# micon_sensor.net
KiCad netlist of a schematic drawn in EAGLE
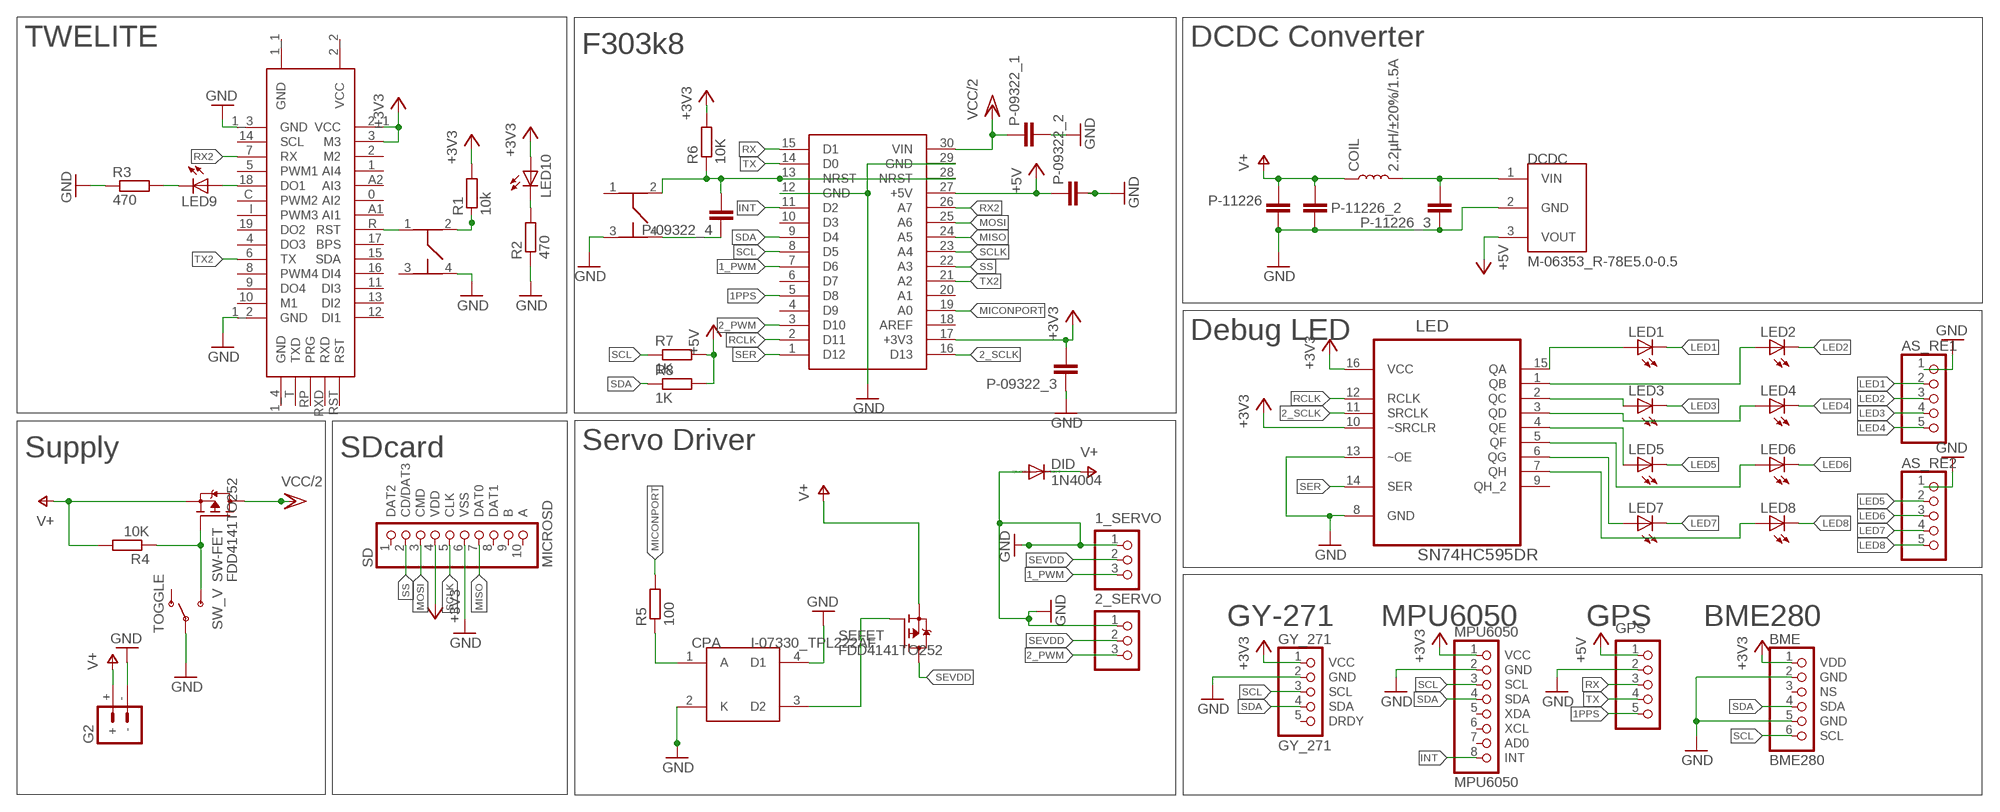
[diagram p0: schematic, sheet 1]

(export (version "E")
  (design (tool "Eeschema 10.0.6"))
  (components
    (comp (ref "1_SERVO")
      (value "B3B-XH-A")
      (footprint "eagle-import:B3B-XH-A")
      (libsource (lib "eagle-import") (part "B3B-XH-A"))
    )
    (comp (ref "2_SERVO")
      (value "B3B-XH-A")
      (footprint "eagle-import:B3B-XH-A")
      (libsource (lib "eagle-import") (part "B3B-XH-A"))
    )
    (comp (ref "AS_RE1")
      (value "PINHD-1X5")
      (footprint "eagle-import:1X05")
      (libsource (lib "eagle-import") (part "PINHD-1X5"))
    )
    (comp (ref "AS_RE2")
      (value "PINHD-1X5")
      (footprint "eagle-import:1X05")
      (libsource (lib "eagle-import") (part "PINHD-1X5"))
    )
    (comp (ref "BME")
      (value "BME280")
      (footprint "eagle-import:1X06")
      (libsource (lib "eagle-import") (part "BME280"))
    )
    (comp (ref "COIL")
      (value "2.2µH/±20%/1.5A")
      (footprint "eagle-import:INDUCTOR_2.2UH")
      (libsource (lib "eagle-import") (part "INDUCTOR-VLF4012AT-2.2UH"))
    )
    (comp (ref "CPA")
      (value "I-07330_TPL222AF")
      (footprint "eagle-import:TLP222AF")
      (libsource (lib "eagle-import") (part "I-07330_TPL222AF"))
    )
    (comp (ref "DCDC")
      (value "M-06353_R-78E5.0-0.5")
      (footprint "eagle-import:R-78E5.0-0.5")
      (libsource (lib "eagle-import") (part "M-06353_R-78E5.0-0.5"))
    )
    (comp (ref "DID")
      (value "1N4004")
      (footprint "eagle-import:DO41-10")
      (libsource (lib "eagle-import") (part "1N4004"))
    )
    (comp (ref "G2")
      (value "BATTERY_CONN_DEANS")
      (footprint "eagle-import:DEANS")
      (libsource (lib "eagle-import") (part "BATTERY_CONN_DEANS"))
    )
    (comp (ref "GPS")
      (value "B5B-XH-A")
      (footprint "eagle-import:B5B-XH-A")
      (libsource (lib "eagle-import") (part "B5B-XH-A"))
    )
    (comp (ref "GY_271")
      (value "GY_271")
      (footprint "eagle-import:1X05")
      (libsource (lib "eagle-import") (part "GY_271"))
    )
    (comp (ref "LED")
      (value "SN74HC595DR")
      (footprint "eagle-import:SOIC127P600X175-16N")
      (fields (field (name "MF") "Texas Instruments"))
      (libsource (lib "eagle-import") (part "SN74HC595DR"))
    )
    (comp (ref "LED1")
      (value "LEDCHIP-LED0603")
      (footprint "eagle-import:CHIP-LED0603")
      (libsource (lib "eagle-import") (part "LEDCHIP-LED0603"))
    )
    (comp (ref "LED2")
      (value "LEDCHIP-LED0603")
      (footprint "eagle-import:CHIP-LED0603")
      (libsource (lib "eagle-import") (part "LEDCHIP-LED0603"))
    )
    (comp (ref "LED3")
      (value "LEDCHIP-LED0603")
      (footprint "eagle-import:CHIP-LED0603")
      (libsource (lib "eagle-import") (part "LEDCHIP-LED0603"))
    )
    (comp (ref "LED4")
      (value "LEDCHIP-LED0603")
      (footprint "eagle-import:CHIP-LED0603")
      (libsource (lib "eagle-import") (part "LEDCHIP-LED0603"))
    )
    (comp (ref "LED5")
      (value "LEDCHIP-LED0603")
      (footprint "eagle-import:CHIP-LED0603")
      (libsource (lib "eagle-import") (part "LEDCHIP-LED0603"))
    )
    (comp (ref "LED6")
      (value "LEDCHIP-LED0603")
      (footprint "eagle-import:CHIP-LED0603")
      (libsource (lib "eagle-import") (part "LEDCHIP-LED0603"))
    )
    (comp (ref "LED7")
      (value "LEDCHIP-LED0603")
      (footprint "eagle-import:CHIP-LED0603")
      (libsource (lib "eagle-import") (part "LEDCHIP-LED0603"))
    )
    (comp (ref "LED8")
      (value "LEDCHIP-LED0603")
      (footprint "eagle-import:CHIP-LED0603")
      (libsource (lib "eagle-import") (part "LEDCHIP-LED0603"))
    )
    (comp (ref "LED9")
      (value "LEDCHIP-LED0603")
      (footprint "eagle-import:CHIP-LED0603")
      (libsource (lib "eagle-import") (part "LEDCHIP-LED0603"))
    )
    (comp (ref "LED10")
      (value "LEDCHIP-LED0603")
      (footprint "eagle-import:CHIP-LED0603")
      (libsource (lib "eagle-import") (part "LEDCHIP-LED0603"))
    )
    (comp (ref "MPU6050")
      (value "MPU6050")
      (footprint "eagle-import:1X08")
      (libsource (lib "eagle-import") (part "MPU6050"))
    )
    (comp (ref "P-09322_1")
      (value "C-EUC0805")
      (footprint "eagle-import:C0805")
      (libsource (lib "eagle-import") (part "C-EUC0805"))
    )
    (comp (ref "P-09322_2")
      (value "C-EUC0805")
      (footprint "eagle-import:C0805")
      (libsource (lib "eagle-import") (part "C-EUC0805"))
    )
    (comp (ref "P-09322_3")
      (value "C-EUC0805")
      (footprint "eagle-import:C0805")
      (libsource (lib "eagle-import") (part "C-EUC0805"))
    )
    (comp (ref "P-09322_4")
      (value "C-EUC0805")
      (footprint "eagle-import:C0805")
      (libsource (lib "eagle-import") (part "C-EUC0805"))
    )
    (comp (ref "P-11226")
      (value "C-EUC0805")
      (footprint "eagle-import:C0805")
      (libsource (lib "eagle-import") (part "C-EUC0805"))
    )
    (comp (ref "P-11226_2")
      (value "C-EUC0805")
      (footprint "eagle-import:C0805")
      (libsource (lib "eagle-import") (part "C-EUC0805"))
    )
    (comp (ref "P-11226_3")
      (value "C-EUC0805")
      (footprint "eagle-import:C0805")
      (libsource (lib "eagle-import") (part "C-EUC0805"))
    )
    (comp (ref "R1")
      (value "10k")
      (footprint "eagle-import:R0805")
      (libsource (lib "eagle-import") (part "R-EU_R0805"))
    )
    (comp (ref "R2")
      (value "470")
      (footprint "eagle-import:R0805")
      (libsource (lib "eagle-import") (part "R-EU_R0805"))
    )
    (comp (ref "R3")
      (value "470")
      (footprint "eagle-import:R0805")
      (libsource (lib "eagle-import") (part "R-EU_R0805"))
    )
    (comp (ref "R4")
      (value "10K")
      (footprint "eagle-import:R0805")
      (libsource (lib "eagle-import") (part "R-EU_R0805"))
    )
    (comp (ref "R5")
      (value "100")
      (footprint "eagle-import:R0805")
      (libsource (lib "eagle-import") (part "R-EU_R0805"))
    )
    (comp (ref "R6")
      (value "10K")
      (footprint "eagle-import:R0805")
      (libsource (lib "eagle-import") (part "R-EU_R0805"))
    )
    (comp (ref "R7")
      (value "1K")
      (footprint "eagle-import:R0805")
      (libsource (lib "eagle-import") (part "R-EU_R0805"))
    )
    (comp (ref "R8")
      (value "1K")
      (footprint "eagle-import:R0805")
      (libsource (lib "eagle-import") (part "R-EU_R0805"))
    )
    (comp (ref "SD")
      (value "MICROSD")
      (footprint "eagle-import:1X10")
      (libsource (lib "eagle-import") (part "MICROSD"))
    )
    (comp (ref "SEFET")
      (value "FDD4141TO252")
      (footprint "eagle-import:TO252")
      (libsource (lib "eagle-import") (part "FDD4141TO252"))
    )
    (comp (ref "SW-FET")
      (value "FDD4141TO252")
      (footprint "eagle-import:TO252")
      (libsource (lib "eagle-import") (part "FDD4141TO252"))
    )
    (comp (ref "SW_MI")
      (value "SWITCH")
      (footprint "eagle-import:SWITCH")
      (libsource (lib "eagle-import") (part "SWITCH"))
    )
    (comp (ref "SW_V")
      (value "TOGGLE")
      (footprint "eagle-import:320-916")
      (libsource (lib "eagle-import") (part "TOGGLE"))
    )
    (comp (ref "TWE_SW")
      (value "SWITCH")
      (footprint "eagle-import:SWITCH")
      (libsource (lib "eagle-import") (part "SWITCH"))
    )
    (comp (ref "U$1")
      (value "TWELITE")
      (footprint "eagle-import:TWELITE_DIP")
      (libsource (lib "eagle-import") (part "TWELITE"))
    )
    (comp (ref "U$3")
      (value "STM32F303K8")
      (footprint "eagle-import:STM32F303K8")
      (libsource (lib "eagle-import") (part "STM32F303K8"))
    )
  )
  (nets
    (net (code "1") (name "+3V3") (class "Default")
      (node (ref "BME") (pin "1") (pinfunction "VDD_1") (pintype "passive"))
      (node (ref "GY_271") (pin "1") (pinfunction "VCC_1") (pintype "passive"))
      (node (ref "LED") (pin "10") (pinfunction "~{SRCLR}_10") (pintype "input"))
      (node (ref "LED") (pin "16") (pinfunction "VCC_16") (pintype "power_in"))
      (node (ref "LED10") (pin "A") (pinfunction "A_A") (pintype "passive"))
      (node (ref "MPU6050") (pin "1") (pinfunction "VCC_1") (pintype "passive"))
      (node (ref "P-09322_3") (pin "2") (pinfunction "2_2") (pintype "passive"))
      (node (ref "R1") (pin "2") (pinfunction "2_2") (pintype "passive"))
      (node (ref "R6") (pin "2") (pinfunction "2_2") (pintype "passive"))
      (node (ref "SD") (pin "4") (pinfunction "VDD_4") (pintype "bidirectional"))
      (node (ref "U$1") (pin "2_1") (pinfunction "VCC_2_1") (pintype "bidirectional"))
      (node (ref "U$1") (pin "3") (pinfunction "M3_3") (pintype "bidirectional"))
      (node (ref "U$3") (pin "17") (pinfunction "+3V3_17") (pintype "power_in"))
    )
    (net (code "2") (name "+5V") (class "Default")
      (node (ref "DCDC") (pin "3") (pinfunction "VOUT_3") (pintype "bidirectional"))
      (node (ref "GPS") (pin "1") (pinfunction "1_1") (pintype "passive"))
      (node (ref "P-09322_2") (pin "1") (pinfunction "1_1") (pintype "passive"))
      (node (ref "R7") (pin "2") (pinfunction "2_2") (pintype "passive"))
      (node (ref "R8") (pin "2") (pinfunction "2_2") (pintype "passive"))
      (node (ref "U$3") (pin "27") (pinfunction "+5V_27") (pintype "power_in"))
    )
    (net (code "3") (name "/AREF") (class "Default")
      (node (ref "U$3") (pin "18") (pinfunction "AREF_18") (pintype "power_in"))
    )
    (net (code "4") (name "1PPS") (class "Default")
      (node (ref "GPS") (pin "5") (pinfunction "5_5") (pintype "passive"))
      (node (ref "U$3") (pin "5") (pinfunction "D8_5") (pintype "bidirectional"))
    )
    (net (code "5") (name "1_PWM") (class "Default")
      (node (ref "1_SERVO") (pin "3") (pinfunction "3_3") (pintype "passive"))
      (node (ref "U$3") (pin "7") (pinfunction "D6_7") (pintype "bidirectional"))
    )
    (net (code "6") (name "2_PWM") (class "Default")
      (node (ref "2_SERVO") (pin "3") (pinfunction "3_3") (pintype "passive"))
      (node (ref "U$3") (pin "3") (pinfunction "D10_3") (pintype "bidirectional"))
    )
    (net (code "7") (name "2_SCLK") (class "Default")
      (node (ref "LED") (pin "11") (pinfunction "SRCLK_11") (pintype "input"))
      (node (ref "U$3") (pin "16") (pinfunction "D13_16") (pintype "bidirectional"))
    )
    (net (code "8") (name "GND") (class "Default")
      (node (ref "1_SERVO") (pin "1") (pinfunction "1_1") (pintype "passive"))
      (node (ref "2_SERVO") (pin "1") (pinfunction "1_1") (pintype "passive"))
      (node (ref "AS_RE1") (pin "1") (pinfunction "1_1") (pintype "passive"))
      (node (ref "AS_RE2") (pin "1") (pinfunction "1_1") (pintype "passive"))
      (node (ref "BME") (pin "2") (pinfunction "GND_2") (pintype "passive"))
      (node (ref "BME") (pin "5") (pinfunction "GND_5") (pintype "passive"))
      (node (ref "CPA") (pin "2") (pinfunction "K_2") (pintype "bidirectional"))
      (node (ref "CPA") (pin "4") (pinfunction "D1_4") (pintype "bidirectional"))
      (node (ref "DCDC") (pin "2") (pinfunction "GND_2") (pintype "bidirectional"))
      (node (ref "DID") (pin "A") (pinfunction "A_A") (pintype "passive"))
      (node (ref "G2") (pin "-") (pinfunction "-_-") (pintype "passive"))
      (node (ref "GPS") (pin "2") (pinfunction "2_2") (pintype "passive"))
      (node (ref "GY_271") (pin "2") (pinfunction "GND_2") (pintype "passive"))
      (node (ref "LED") (pin "13") (pinfunction "~{OE}_13") (pintype "input"))
      (node (ref "LED") (pin "8") (pinfunction "GND_8") (pintype "passive"))
      (node (ref "MPU6050") (pin "2") (pinfunction "GND_2") (pintype "passive"))
      (node (ref "P-09322_1") (pin "2") (pinfunction "2_2") (pintype "passive"))
      (node (ref "P-09322_2") (pin "2") (pinfunction "2_2") (pintype "passive"))
      (node (ref "P-09322_3") (pin "1") (pinfunction "1_1") (pintype "passive"))
      (node (ref "P-11226") (pin "1") (pinfunction "1_1") (pintype "passive"))
      (node (ref "P-11226_2") (pin "1") (pinfunction "1_1") (pintype "passive"))
      (node (ref "P-11226_3") (pin "1") (pinfunction "1_1") (pintype "passive"))
      (node (ref "R2") (pin "1") (pinfunction "1_1") (pintype "passive"))
      (node (ref "R3") (pin "1") (pinfunction "1_1") (pintype "passive"))
      (node (ref "SD") (pin "6") (pinfunction "VSS_6") (pintype "bidirectional"))
      (node (ref "SW_MI") (pin "3") (pinfunction "P$3_3") (pintype "bidirectional"))
      (node (ref "SW_V") (pin "2") (pinfunction "2_2") (pintype "passive"))
      (node (ref "TWE_SW") (pin "4") (pinfunction "P$4_4") (pintype "bidirectional"))
      (node (ref "U$1") (pin "1_2") (pinfunction "GND_1_2") (pintype "bidirectional"))
      (node (ref "U$1") (pin "1_3") (pinfunction "GND_1_3") (pintype "bidirectional"))
      (node (ref "U$3") (pin "12") (pinfunction "GND_12") (pintype "power_in"))
      (node (ref "U$3") (pin "29") (pinfunction "GND_29") (pintype "power_in"))
    )
    (net (code "9") (name "INT") (class "Default")
      (node (ref "MPU6050") (pin "8") (pinfunction "INT_8") (pintype "passive"))
      (node (ref "U$3") (pin "11") (pinfunction "D2_11") (pintype "bidirectional"))
    )
    (net (code "10") (name "LED1") (class "Default")
      (node (ref "AS_RE1") (pin "2") (pinfunction "2_2") (pintype "passive"))
      (node (ref "LED1") (pin "C") (pinfunction "C_C") (pintype "passive"))
    )
    (net (code "11") (name "LED2") (class "Default")
      (node (ref "AS_RE1") (pin "3") (pinfunction "3_3") (pintype "passive"))
      (node (ref "LED2") (pin "C") (pinfunction "C_C") (pintype "passive"))
    )
    (net (code "12") (name "LED3") (class "Default")
      (node (ref "AS_RE1") (pin "4") (pinfunction "4_4") (pintype "passive"))
      (node (ref "LED3") (pin "C") (pinfunction "C_C") (pintype "passive"))
    )
    (net (code "13") (name "LED4") (class "Default")
      (node (ref "AS_RE1") (pin "5") (pinfunction "5_5") (pintype "passive"))
      (node (ref "LED4") (pin "C") (pinfunction "C_C") (pintype "passive"))
    )
    (net (code "14") (name "LED5") (class "Default")
      (node (ref "AS_RE2") (pin "2") (pinfunction "2_2") (pintype "passive"))
      (node (ref "LED5") (pin "C") (pinfunction "C_C") (pintype "passive"))
    )
    (net (code "15") (name "LED6") (class "Default")
      (node (ref "AS_RE2") (pin "3") (pinfunction "3_3") (pintype "passive"))
      (node (ref "LED6") (pin "C") (pinfunction "C_C") (pintype "passive"))
    )
    (net (code "16") (name "LED7") (class "Default")
      (node (ref "AS_RE2") (pin "4") (pinfunction "4_4") (pintype "passive"))
      (node (ref "LED7") (pin "C") (pinfunction "C_C") (pintype "passive"))
    )
    (net (code "17") (name "LED8") (class "Default")
      (node (ref "AS_RE2") (pin "5") (pinfunction "5_5") (pintype "passive"))
      (node (ref "LED8") (pin "C") (pinfunction "C_C") (pintype "passive"))
    )
    (net (code "18") (name "MICONPORT") (class "Default")
      (node (ref "R5") (pin "2") (pinfunction "2_2") (pintype "passive"))
      (node (ref "U$3") (pin "19") (pinfunction "A0_19") (pintype "bidirectional"))
    )
    (net (code "19") (name "MISO") (class "Default")
      (node (ref "SD") (pin "7") (pinfunction "DAT0_7") (pintype "bidirectional"))
      (node (ref "U$3") (pin "24") (pinfunction "A5_24") (pintype "bidirectional"))
    )
    (net (code "20") (name "MOSI") (class "Default")
      (node (ref "SD") (pin "3") (pinfunction "CMD_3") (pintype "bidirectional"))
      (node (ref "U$3") (pin "25") (pinfunction "A6_25") (pintype "bidirectional"))
    )
    (net (code "21") (name "Net-(COIL-2)") (class "Default")
      (node (ref "COIL") (pin "P$2") (pinfunction "2_P$2") (pintype "passive"))
      (node (ref "DCDC") (pin "1") (pinfunction "VIN_1") (pintype "bidirectional"))
      (node (ref "P-11226_3") (pin "2") (pinfunction "2_2") (pintype "passive"))
    )
    (net (code "22") (name "Net-(CPA-A)") (class "Default")
      (node (ref "CPA") (pin "1") (pinfunction "A_1") (pintype "bidirectional"))
      (node (ref "R5") (pin "1") (pinfunction "1_1") (pintype "passive"))
    )
    (net (code "23") (name "Net-(CPA-D2)") (class "Default")
      (node (ref "CPA") (pin "3") (pinfunction "D2_3") (pintype "bidirectional"))
      (node (ref "SEFET") (pin "1") (pinfunction "G_1") (pintype "passive"))
    )
    (net (code "24") (name "Net-(LED-QA)") (class "Default")
      (node (ref "LED") (pin "15") (pinfunction "QA_15") (pintype "output"))
      (node (ref "LED1") (pin "A") (pinfunction "A_A") (pintype "passive"))
    )
    (net (code "25") (name "Net-(LED-QB)") (class "Default")
      (node (ref "LED") (pin "1") (pinfunction "QB_1") (pintype "output"))
      (node (ref "LED2") (pin "A") (pinfunction "A_A") (pintype "passive"))
    )
    (net (code "26") (name "Net-(LED-QC)") (class "Default")
      (node (ref "LED") (pin "2") (pinfunction "QC_2") (pintype "output"))
      (node (ref "LED3") (pin "A") (pinfunction "A_A") (pintype "passive"))
    )
    (net (code "27") (name "Net-(LED-QD)") (class "Default")
      (node (ref "LED") (pin "3") (pinfunction "QD_3") (pintype "output"))
      (node (ref "LED4") (pin "A") (pinfunction "A_A") (pintype "passive"))
    )
    (net (code "28") (name "Net-(LED-QE)") (class "Default")
      (node (ref "LED") (pin "4") (pinfunction "QE_4") (pintype "output"))
      (node (ref "LED5") (pin "A") (pinfunction "A_A") (pintype "passive"))
    )
    (net (code "29") (name "Net-(LED-QF)") (class "Default")
      (node (ref "LED") (pin "5") (pinfunction "QF_5") (pintype "output"))
      (node (ref "LED6") (pin "A") (pinfunction "A_A") (pintype "passive"))
    )
    (net (code "30") (name "Net-(LED-QG)") (class "Default")
      (node (ref "LED") (pin "6") (pinfunction "QG_6") (pintype "output"))
      (node (ref "LED7") (pin "A") (pinfunction "A_A") (pintype "passive"))
    )
    (net (code "31") (name "Net-(LED-QH)") (class "Default")
      (node (ref "LED") (pin "7") (pinfunction "QH_7") (pintype "output"))
      (node (ref "LED8") (pin "A") (pinfunction "A_A") (pintype "passive"))
    )
    (net (code "32") (name "Net-(LED9-PadC)") (class "Default")
      (node (ref "LED9") (pin "C") (pinfunction "C_C") (pintype "passive"))
      (node (ref "R3") (pin "2") (pinfunction "2_2") (pintype "passive"))
    )
    (net (code "33") (name "Net-(LED10-PadC)") (class "Default")
      (node (ref "LED10") (pin "C") (pinfunction "C_C") (pintype "passive"))
      (node (ref "R2") (pin "2") (pinfunction "2_2") (pintype "passive"))
    )
    (net (code "34") (name "Net-(SW-FET-G)") (class "Default")
      (node (ref "R4") (pin "1") (pinfunction "1_1") (pintype "passive"))
      (node (ref "SW-FET") (pin "1") (pinfunction "G_1") (pintype "passive"))
      (node (ref "SW_V") (pin "3") (pinfunction "3_3") (pintype "passive"))
    )
    (net (code "35") (name "Net-(SW_MI-P$2)") (class "Default")
      (node (ref "P-09322_4") (pin "2") (pinfunction "2_2") (pintype "passive"))
      (node (ref "R6") (pin "1") (pinfunction "1_1") (pintype "passive"))
      (node (ref "SW_MI") (pin "2") (pinfunction "P$2_2") (pintype "bidirectional"))
      (node (ref "U$3") (pin "13") (pinfunction "NRST_13") (pintype "input"))
      (node (ref "U$3") (pin "28") (pinfunction "NRST_28") (pintype "input"))
    )
    (net (code "36") (name "Net-(SW_MI-P$4)") (class "Default")
      (node (ref "P-09322_4") (pin "1") (pinfunction "1_1") (pintype "passive"))
      (node (ref "SW_MI") (pin "4") (pinfunction "P$4_4") (pintype "bidirectional"))
    )
    (net (code "37") (name "Net-(TWE_SW-P$1)") (class "Default")
      (node (ref "TWE_SW") (pin "1") (pinfunction "P$1_1") (pintype "bidirectional"))
      (node (ref "U$1") (pin "R") (pinfunction "RST_R") (pintype "bidirectional"))
    )
    (net (code "38") (name "Net-(TWE_SW-P$2)") (class "Default")
      (node (ref "R1") (pin "1") (pinfunction "1_1") (pintype "passive"))
      (node (ref "TWE_SW") (pin "2") (pinfunction "P$2_2") (pintype "bidirectional"))
    )
    (net (code "39") (name "Net-(U$1-DO1)") (class "Default")
      (node (ref "LED9") (pin "A") (pinfunction "A_A") (pintype "passive"))
      (node (ref "U$1") (pin "18") (pinfunction "DO1_18") (pintype "bidirectional"))
    )
    (net (code "40") (name "RCLK") (class "Default")
      (node (ref "LED") (pin "12") (pinfunction "RCLK_12") (pintype "input"))
      (node (ref "U$3") (pin "2") (pinfunction "D11_2") (pintype "bidirectional"))
    )
    (net (code "41") (name "RX") (class "Default")
      (node (ref "GPS") (pin "3") (pinfunction "3_3") (pintype "passive"))
      (node (ref "U$3") (pin "15") (pinfunction "D1_15") (pintype "bidirectional"))
    )
    (net (code "42") (name "RX2") (class "Default")
      (node (ref "U$1") (pin "7") (pinfunction "RX_7") (pintype "bidirectional"))
      (node (ref "U$3") (pin "26") (pinfunction "A7_26") (pintype "bidirectional"))
    )
    (net (code "43") (name "SCL") (class "Default")
      (node (ref "BME") (pin "6") (pinfunction "SCL_6") (pintype "passive"))
      (node (ref "GY_271") (pin "3") (pinfunction "SCL_3") (pintype "passive"))
      (node (ref "MPU6050") (pin "3") (pinfunction "SCL_3") (pintype "passive"))
      (node (ref "R7") (pin "1") (pinfunction "1_1") (pintype "passive"))
      (node (ref "U$3") (pin "8") (pinfunction "D5_8") (pintype "bidirectional"))
    )
    (net (code "44") (name "SCLK") (class "Default")
      (node (ref "SD") (pin "5") (pinfunction "CLK_5") (pintype "bidirectional"))
      (node (ref "U$3") (pin "23") (pinfunction "A4_23") (pintype "bidirectional"))
    )
    (net (code "45") (name "SDA") (class "Default")
      (node (ref "BME") (pin "4") (pinfunction "SDA_4") (pintype "passive"))
      (node (ref "GY_271") (pin "4") (pinfunction "SDA_4") (pintype "passive"))
      (node (ref "MPU6050") (pin "4") (pinfunction "SDA_4") (pintype "passive"))
      (node (ref "R8") (pin "1") (pinfunction "1_1") (pintype "passive"))
      (node (ref "U$3") (pin "9") (pinfunction "D4_9") (pintype "bidirectional"))
    )
    (net (code "46") (name "SER") (class "Default")
      (node (ref "LED") (pin "14") (pinfunction "SER_14") (pintype "input"))
      (node (ref "U$3") (pin "1") (pinfunction "D12_1") (pintype "bidirectional"))
    )
    (net (code "47") (name "SEVDD") (class "Default")
      (node (ref "1_SERVO") (pin "2") (pinfunction "2_2") (pintype "passive"))
      (node (ref "2_SERVO") (pin "2") (pinfunction "2_2") (pintype "passive"))
      (node (ref "SEFET") (pin "3") (pinfunction "D_3") (pintype "passive"))
    )
    (net (code "48") (name "SS") (class "Default")
      (node (ref "SD") (pin "2") (pinfunction "CD/DAT3_2") (pintype "bidirectional"))
      (node (ref "U$3") (pin "22") (pinfunction "A3_22") (pintype "bidirectional"))
    )
    (net (code "49") (name "TX") (class "Default")
      (node (ref "GPS") (pin "4") (pinfunction "4_4") (pintype "passive"))
      (node (ref "U$3") (pin "14") (pinfunction "D0_14") (pintype "bidirectional"))
    )
    (net (code "50") (name "TX2") (class "Default")
      (node (ref "U$1") (pin "6") (pinfunction "TX_6") (pintype "bidirectional"))
      (node (ref "U$3") (pin "21") (pinfunction "A2_21") (pintype "bidirectional"))
    )
    (net (code "51") (name "V+") (class "Default")
      (node (ref "COIL") (pin "P$1") (pinfunction "1_P$1") (pintype "passive"))
      (node (ref "DID") (pin "C") (pinfunction "C_C") (pintype "passive"))
      (node (ref "G2") (pin "+") (pinfunction "+_+") (pintype "passive"))
      (node (ref "P-11226") (pin "2") (pinfunction "2_2") (pintype "passive"))
      (node (ref "P-11226_2") (pin "2") (pinfunction "2_2") (pintype "passive"))
      (node (ref "R4") (pin "2") (pinfunction "2_2") (pintype "passive"))
      (node (ref "SEFET") (pin "2") (pinfunction "S_2") (pintype "passive"))
      (node (ref "SW-FET") (pin "2") (pinfunction "S_2") (pintype "passive"))
    )
    (net (code "52") (name "VCC{slash}2") (class "Default")
      (node (ref "P-09322_1") (pin "1") (pinfunction "1_1") (pintype "passive"))
      (node (ref "SW-FET") (pin "3") (pinfunction "D_3") (pintype "passive"))
      (node (ref "U$3") (pin "30") (pinfunction "VIN_30") (pintype "power_in"))
    )
    (net (code "53") (name "unconnected-(BME-NS-Pad3)") (class "Default")
      (node (ref "BME") (pin "3") (pinfunction "NS_3") (pintype "passive"))
    )
    (net (code "54") (name "unconnected-(GY_271-DRDY-Pad5)") (class "Default")
      (node (ref "GY_271") (pin "5") (pinfunction "DRDY_5") (pintype "passive"))
    )
    (net (code "55") (name "unconnected-(LED-QH_2-Pad9)") (class "Default")
      (node (ref "LED") (pin "9") (pinfunction "QH_2_9") (pintype "output"))
    )
    (net (code "56") (name "unconnected-(MPU6050-AD0-Pad7)") (class "Default")
      (node (ref "MPU6050") (pin "7") (pinfunction "AD0_7") (pintype "passive"))
    )
    (net (code "57") (name "unconnected-(MPU6050-XCL-Pad6)") (class "Default")
      (node (ref "MPU6050") (pin "6") (pinfunction "XCL_6") (pintype "passive"))
    )
    (net (code "58") (name "unconnected-(MPU6050-XDA-Pad5)") (class "Default")
      (node (ref "MPU6050") (pin "5") (pinfunction "XDA_5") (pintype "passive"))
    )
    (net (code "59") (name "unconnected-(SD-A-Pad10)") (class "Default")
      (node (ref "SD") (pin "10") (pinfunction "A_10") (pintype "bidirectional"))
    )
    (net (code "60") (name "unconnected-(SD-B-Pad9)") (class "Default")
      (node (ref "SD") (pin "9") (pinfunction "B_9") (pintype "bidirectional"))
    )
    (net (code "61") (name "unconnected-(SD-DAT1-Pad8)") (class "Default")
      (node (ref "SD") (pin "8") (pinfunction "DAT1_8") (pintype "bidirectional"))
    )
    (net (code "62") (name "unconnected-(SD-DAT2-Pad1)") (class "Default")
      (node (ref "SD") (pin "1") (pinfunction "DAT2_1") (pintype "bidirectional"))
    )
    (net (code "63") (name "unconnected-(SW_MI-P$1-Pad1)") (class "Default")
      (node (ref "SW_MI") (pin "1") (pinfunction "P$1_1") (pintype "bidirectional"))
    )
    (net (code "64") (name "unconnected-(SW_V-Pad1)") (class "Default")
      (node (ref "SW_V") (pin "1") (pinfunction "1_1") (pintype "passive"))
    )
    (net (code "65") (name "unconnected-(TWE_SW-P$3-Pad3)") (class "Default")
      (node (ref "TWE_SW") (pin "3") (pinfunction "P$3_3") (pintype "bidirectional"))
    )
    (net (code "66") (name "unconnected-(U$1-AI1-PadA1)") (class "Default")
      (node (ref "U$1") (pin "A1") (pinfunction "AI1_A1") (pintype "bidirectional"))
    )
    (net (code "67") (name "unconnected-(U$1-AI2-Pad0)") (class "Default")
      (node (ref "U$1") (pin "0") (pinfunction "AI2_0") (pintype "bidirectional"))
    )
    (net (code "68") (name "unconnected-(U$1-AI3-PadA2)") (class "Default")
      (node (ref "U$1") (pin "A2") (pinfunction "AI3_A2") (pintype "bidirectional"))
    )
    (net (code "69") (name "unconnected-(U$1-AI4-Pad1)") (class "Default")
      (node (ref "U$1") (pin "1") (pinfunction "AI4_1") (pintype "bidirectional"))
    )
    (net (code "70") (name "unconnected-(U$1-BPS-Pad17)") (class "Default")
      (node (ref "U$1") (pin "17") (pinfunction "BPS_17") (pintype "bidirectional"))
    )
    (net (code "71") (name "unconnected-(U$1-DI1-Pad12)") (class "Default")
      (node (ref "U$1") (pin "12") (pinfunction "DI1_12") (pintype "bidirectional"))
    )
    (net (code "72") (name "unconnected-(U$1-DI2-Pad13)") (class "Default")
      (node (ref "U$1") (pin "13") (pinfunction "DI2_13") (pintype "bidirectional"))
    )
    (net (code "73") (name "unconnected-(U$1-DI3-Pad11)") (class "Default")
      (node (ref "U$1") (pin "11") (pinfunction "DI3_11") (pintype "bidirectional"))
    )
    (net (code "74") (name "unconnected-(U$1-DI4-Pad16)") (class "Default")
      (node (ref "U$1") (pin "16") (pinfunction "DI4_16") (pintype "bidirectional"))
    )
    (net (code "75") (name "unconnected-(U$1-DO2-Pad19)") (class "Default")
      (node (ref "U$1") (pin "19") (pinfunction "DO2_19") (pintype "bidirectional"))
    )
    (net (code "76") (name "unconnected-(U$1-DO3-Pad4)") (class "Default")
      (node (ref "U$1") (pin "4") (pinfunction "DO3_4") (pintype "bidirectional"))
    )
    (net (code "77") (name "unconnected-(U$1-DO4-Pad9)") (class "Default")
      (node (ref "U$1") (pin "9") (pinfunction "DO4_9") (pintype "bidirectional"))
    )
    (net (code "78") (name "unconnected-(U$1-GND-Pad1_1)") (class "Default")
      (node (ref "U$1") (pin "1_1") (pinfunction "GND_1_1") (pintype "bidirectional"))
    )
    (net (code "79") (name "unconnected-(U$1-GND-Pad1_4)") (class "Default")
      (node (ref "U$1") (pin "1_4") (pinfunction "GND_1_4") (pintype "bidirectional"))
    )
    (net (code "80") (name "unconnected-(U$1-M1-Pad10)") (class "Default")
      (node (ref "U$1") (pin "10") (pinfunction "M1_10") (pintype "bidirectional"))
    )
    (net (code "81") (name "unconnected-(U$1-M2-Pad2)") (class "Default")
      (node (ref "U$1") (pin "2") (pinfunction "M2_2") (pintype "bidirectional"))
    )
    (net (code "82") (name "unconnected-(U$1-PRG-PadRP)") (class "Default")
      (node (ref "U$1") (pin "RP") (pinfunction "PRG_RP") (pintype "bidirectional"))
    )
    (net (code "83") (name "unconnected-(U$1-PWM1-Pad5)") (class "Default")
      (node (ref "U$1") (pin "5") (pinfunction "PWM1_5") (pintype "bidirectional"))
    )
    (net (code "84") (name "unconnected-(U$1-PWM2-PadC)") (class "Default")
      (node (ref "U$1") (pin "C") (pinfunction "PWM2_C") (pintype "bidirectional"))
    )
    (net (code "85") (name "unconnected-(U$1-PWM3-PadI)") (class "Default")
      (node (ref "U$1") (pin "I") (pinfunction "PWM3_I") (pintype "bidirectional"))
    )
    (net (code "86") (name "unconnected-(U$1-PWM4-Pad8)") (class "Default")
      (node (ref "U$1") (pin "8") (pinfunction "PWM4_8") (pintype "bidirectional"))
    )
    (net (code "87") (name "unconnected-(U$1-PadRST)") (class "Default")
      (node (ref "U$1") (pin "RST") (pinfunction "RST_RST") (pintype "bidirectional"))
    )
    (net (code "88") (name "unconnected-(U$1-PadRXD)") (class "Default")
      (node (ref "U$1") (pin "RXD") (pinfunction "RXD_RXD") (pintype "bidirectional"))
    )
    (net (code "89") (name "unconnected-(U$1-SCL-Pad14)") (class "Default")
      (node (ref "U$1") (pin "14") (pinfunction "SCL_14") (pintype "bidirectional"))
    )
    (net (code "90") (name "unconnected-(U$1-SDA-Pad15)") (class "Default")
      (node (ref "U$1") (pin "15") (pinfunction "SDA_15") (pintype "bidirectional"))
    )
    (net (code "91") (name "unconnected-(U$1-TXD-PadT)") (class "Default")
      (node (ref "U$1") (pin "T") (pinfunction "TXD_T") (pintype "bidirectional"))
    )
    (net (code "92") (name "unconnected-(U$1-VCC-Pad2_2)") (class "Default")
      (node (ref "U$1") (pin "2_2") (pinfunction "VCC_2_2") (pintype "bidirectional"))
    )
    (net (code "93") (name "unconnected-(U$3-A1-Pad20)") (class "Default")
      (node (ref "U$3") (pin "20") (pinfunction "A1_20") (pintype "bidirectional"))
    )
    (net (code "94") (name "unconnected-(U$3-D3-Pad10)") (class "Default")
      (node (ref "U$3") (pin "10") (pinfunction "D3_10") (pintype "bidirectional"))
    )
    (net (code "95") (name "unconnected-(U$3-D7-Pad6)") (class "Default")
      (node (ref "U$3") (pin "6") (pinfunction "D7_6") (pintype "bidirectional"))
    )
    (net (code "96") (name "unconnected-(U$3-D9-Pad4)") (class "Default")
      (node (ref "U$3") (pin "4") (pinfunction "D9_4") (pintype "bidirectional"))
    )
  )
)
